# logica.net
KiCad netlist of a schematic drawn in EAGLE
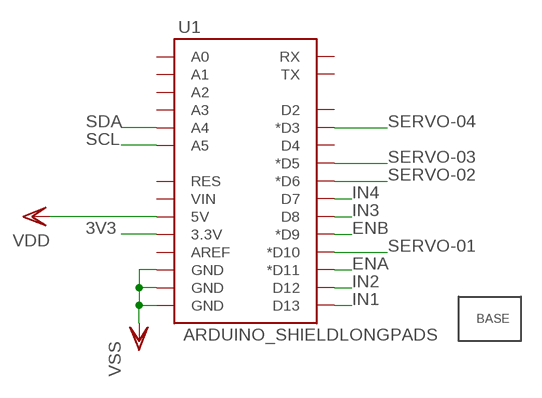
[diagram p0: schematic, sheet 1]
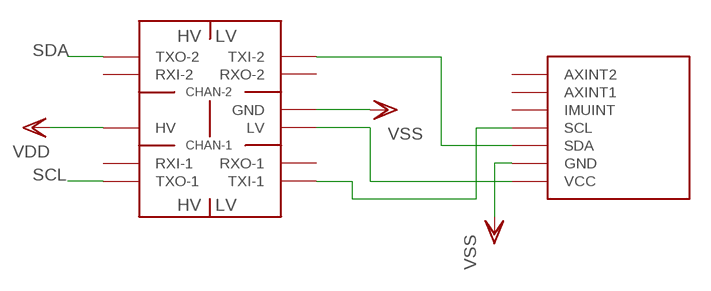
[diagram p1: schematic, sheet 2]
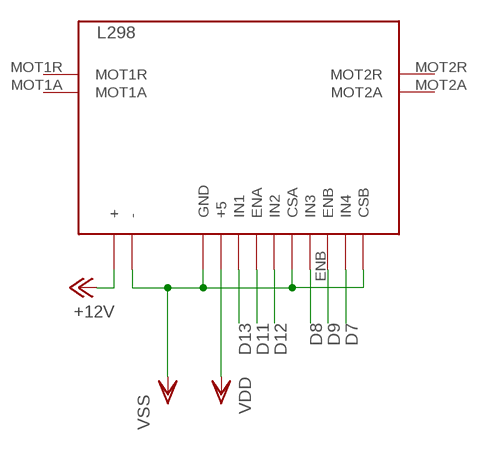
[diagram p2: schematic, sheet 3]

(export (version "E")
  (design (tool "Eeschema 10.0.6"))
  (components
    (comp (ref "L298")
      (value "UK1122")
      (footprint "eagle-import:UK1122")
      (libsource (lib "eagle-import") (part "UK1122"))
    )
    (comp (ref "U$4")
      (value "BASE")
      (footprint "eagle-import:BASE")
      (libsource (lib "eagle-import") (part "BASE"))
    )
    (comp (ref "U1")
      (value "ARDUINO_SHIELDLONGPADS")
      (footprint "eagle-import:DUEMILANOVE_SHIELD_LONGPADS")
      (libsource (lib "eagle-import") (part "ARDUINO_SHIELDLONGPADS"))
    )
    (comp (ref "U$1")
      (value "LOGIC-LEVEL-CONVERTER")
      (footprint "eagle-import:LEVEL-CONVERTER")
      (libsource (lib "eagle-import") (part "LOGIC-LEVEL-CONVERTER"))
    )
    (comp (ref "U$2")
      (value "IMU3000COMBO")
      (footprint "eagle-import:IMU3000-COMBO")
      (libsource (lib "eagle-import") (part "IMU3000COMBO"))
    )
  )
  (nets
    (net (code "1") (name "+12V") (class "Default")
      (node (ref "L298") (pin "+") (pinfunction "+_+") (pintype "power_in"))
    )
    (net (code "2") (name "3V3") (class "Default")
      (node (ref "U$1") (pin "P$3") (pinfunction "LV_P$3") (pintype "power_in"))
      (node (ref "U$2") (pin "3V3") (pinfunction "VCC_3V3") (pintype "power_in"))
      (node (ref "U1") (pin "3.3V") (pinfunction "3.3V_3.3V") (pintype "bidirectional"))
    )
    (net (code "3") (name "D7") (class "Default")
      (node (ref "L298") (pin "IN4") (pinfunction "IN4_IN4") (pintype "input"))
      (node (ref "U1") (pin "D7") (pinfunction "D7_D7") (pintype "bidirectional"))
    )
    (net (code "4") (name "D8") (class "Default")
      (node (ref "L298") (pin "IN3") (pinfunction "IN3_IN3") (pintype "input"))
      (node (ref "U1") (pin "D8") (pinfunction "D8_D8") (pintype "bidirectional"))
    )
    (net (code "5") (name "D9") (class "Default")
      (node (ref "L298") (pin "ENB") (pinfunction "ENB_ENB") (pintype "bidirectional"))
      (node (ref "U1") (pin "D9") (pinfunction "*D9_D9") (pintype "bidirectional"))
    )
    (net (code "6") (name "D11") (class "Default")
      (node (ref "L298") (pin "ENA") (pinfunction "ENA_ENA") (pintype "input"))
      (node (ref "U1") (pin "D11") (pinfunction "*D11_D11") (pintype "bidirectional"))
    )
    (net (code "7") (name "D12") (class "Default")
      (node (ref "L298") (pin "EN2") (pinfunction "IN2_EN2") (pintype "input"))
      (node (ref "U1") (pin "D12") (pinfunction "D12_D12") (pintype "bidirectional"))
    )
    (net (code "8") (name "D13") (class "Default")
      (node (ref "L298") (pin "IN1") (pinfunction "IN1_IN1") (pintype "input"))
      (node (ref "U1") (pin "D13") (pinfunction "D13_D13") (pintype "bidirectional"))
    )
    (net (code "9") (name "Net-(U$1-TXI-1)") (class "Default")
      (node (ref "U$1") (pin "P$1") (pinfunction "TXI-1_P$1") (pintype "bidirectional"))
      (node (ref "U$2") (pin "SCL") (pinfunction "SCL_SCL") (pintype "bidirectional"))
    )
    (net (code "10") (name "Net-(U$1-TXI-2)") (class "Default")
      (node (ref "U$1") (pin "P$6") (pinfunction "TXI-2_P$6") (pintype "bidirectional"))
      (node (ref "U$2") (pin "SDA") (pinfunction "SDA_SDA") (pintype "bidirectional"))
    )
    (net (code "11") (name "SCL") (class "Default")
      (node (ref "U$1") (pin "P$12") (pinfunction "TXO-1_P$12") (pintype "bidirectional"))
      (node (ref "U1") (pin "A5") (pinfunction "A5_A5") (pintype "bidirectional"))
    )
    (net (code "12") (name "SDA") (class "Default")
      (node (ref "U$1") (pin "P$7") (pinfunction "TXO-2_P$7") (pintype "bidirectional"))
      (node (ref "U1") (pin "A4") (pinfunction "A4_A4") (pintype "bidirectional"))
    )
    (net (code "13") (name "SERVO-01") (class "Default")
      (node (ref "U1") (pin "D10") (pinfunction "*D10_D10") (pintype "bidirectional"))
    )
    (net (code "14") (name "SERVO-02") (class "Default")
      (node (ref "U1") (pin "D6") (pinfunction "*D6_D6") (pintype "bidirectional"))
    )
    (net (code "15") (name "SERVO-03") (class "Default")
      (node (ref "U1") (pin "D5") (pinfunction "*D5_D5") (pintype "bidirectional"))
    )
    (net (code "16") (name "SERVO-04") (class "Default")
      (node (ref "U1") (pin "D3") (pinfunction "*D3_D3") (pintype "bidirectional"))
    )
    (net (code "17") (name "VDD") (class "Default")
      (node (ref "L298") (pin "+5") (pinfunction "+5_+5") (pintype "power_in"))
      (node (ref "U$1") (pin "P$10") (pinfunction "HV_P$10") (pintype "power_in"))
      (node (ref "U1") (pin "5V") (pinfunction "5V_5V") (pintype "bidirectional"))
    )
    (net (code "18") (name "VSS") (class "Default")
      (node (ref "L298") (pin "-") (pinfunction "-_-") (pintype "power_in"))
      (node (ref "L298") (pin "CSA") (pinfunction "CSA_CSA") (pintype "output"))
      (node (ref "L298") (pin "CSB") (pinfunction "CSB_CSB") (pintype "output"))
      (node (ref "L298") (pin "GND") (pinfunction "GND_GND") (pintype "power_in"))
      (node (ref "U$1") (pin "P$4") (pinfunction "GND_P$4") (pintype "power_in"))
      (node (ref "U$2") (pin "VSS") (pinfunction "GND_VSS") (pintype "power_in"))
      (node (ref "U1") (pin "GND@0") (pinfunction "GND_GND@0") (pintype "bidirectional"))
      (node (ref "U1") (pin "GND@1") (pinfunction "GND_GND@1") (pintype "bidirectional"))
      (node (ref "U1") (pin "GND@2") (pinfunction "GND_GND@2") (pintype "bidirectional"))
    )
    (net (code "19") (name "unconnected-(L298-PadMOT1A)") (class "Default")
      (node (ref "L298") (pin "MOT1A") (pinfunction "MOT1A_MOT1A") (pintype "bidirectional"))
    )
    (net (code "20") (name "unconnected-(L298-PadMOT1R)") (class "Default")
      (node (ref "L298") (pin "MOT1R") (pinfunction "MOT1R_MOT1R") (pintype "bidirectional"))
    )
    (net (code "21") (name "unconnected-(L298-PadMOT2A)") (class "Default")
      (node (ref "L298") (pin "MOT2A") (pinfunction "MOT2A_MOT2A") (pintype "bidirectional"))
    )
    (net (code "22") (name "unconnected-(L298-PadMOT2R)") (class "Default")
      (node (ref "L298") (pin "MOT2R") (pinfunction "MOT2R_MOT2R") (pintype "bidirectional"))
    )
    (net (code "23") (name "unconnected-(U$1-PadP$9)") (class "Default")
      (node (ref "U$1") (pin "P$9") (pintype "power_in"))
    )
    (net (code "24") (name "unconnected-(U$1-RXI-1-PadP$11)") (class "Default")
      (node (ref "U$1") (pin "P$11") (pinfunction "RXI-1_P$11") (pintype "bidirectional"))
    )
    (net (code "25") (name "unconnected-(U$1-RXI-2-PadP$8)") (class "Default")
      (node (ref "U$1") (pin "P$8") (pinfunction "RXI-2_P$8") (pintype "bidirectional"))
    )
    (net (code "26") (name "unconnected-(U$1-RXO-1-PadP$2)") (class "Default")
      (node (ref "U$1") (pin "P$2") (pinfunction "RXO-1_P$2") (pintype "bidirectional"))
    )
    (net (code "27") (name "unconnected-(U$1-RXO-2-PadP$5)") (class "Default")
      (node (ref "U$1") (pin "P$5") (pinfunction "RXO-2_P$5") (pintype "bidirectional"))
    )
    (net (code "28") (name "unconnected-(U$2-PadAXINT1)") (class "Default")
      (node (ref "U$2") (pin "AXINT1") (pinfunction "AXINT1_AXINT1") (pintype "bidirectional"))
    )
    (net (code "29") (name "unconnected-(U$2-PadAXINT2)") (class "Default")
      (node (ref "U$2") (pin "AXINT2") (pinfunction "AXINT2_AXINT2") (pintype "bidirectional"))
    )
    (net (code "30") (name "unconnected-(U$2-PadIMUINT)") (class "Default")
      (node (ref "U$2") (pin "IMUINT") (pinfunction "IMUINT_IMUINT") (pintype "bidirectional"))
    )
    (net (code "31") (name "unconnected-(U1-PadA0)") (class "Default")
      (node (ref "U1") (pin "A0") (pinfunction "A0_A0") (pintype "bidirectional"))
    )
    (net (code "32") (name "unconnected-(U1-PadA1)") (class "Default")
      (node (ref "U1") (pin "A1") (pinfunction "A1_A1") (pintype "bidirectional"))
    )
    (net (code "33") (name "unconnected-(U1-PadA2)") (class "Default")
      (node (ref "U1") (pin "A2") (pinfunction "A2_A2") (pintype "bidirectional"))
    )
    (net (code "34") (name "unconnected-(U1-PadA3)") (class "Default")
      (node (ref "U1") (pin "A3") (pinfunction "A3_A3") (pintype "bidirectional"))
    )
    (net (code "35") (name "unconnected-(U1-PadAREF)") (class "Default")
      (node (ref "U1") (pin "AREF") (pinfunction "AREF_AREF") (pintype "bidirectional"))
    )
    (net (code "36") (name "unconnected-(U1-PadD2)") (class "Default")
      (node (ref "U1") (pin "D2") (pinfunction "D2_D2") (pintype "bidirectional"))
    )
    (net (code "37") (name "unconnected-(U1-PadD4)") (class "Default")
      (node (ref "U1") (pin "D4") (pinfunction "D4_D4") (pintype "bidirectional"))
    )
    (net (code "38") (name "unconnected-(U1-PadRES)") (class "Default")
      (node (ref "U1") (pin "RES") (pinfunction "RES_RES") (pintype "bidirectional"))
    )
    (net (code "39") (name "unconnected-(U1-PadRX)") (class "Default")
      (node (ref "U1") (pin "RX") (pinfunction "RX_RX") (pintype "bidirectional"))
    )
    (net (code "40") (name "unconnected-(U1-PadTX)") (class "Default")
      (node (ref "U1") (pin "TX") (pinfunction "TX_TX") (pintype "bidirectional"))
    )
    (net (code "41") (name "unconnected-(U1-PadVIN)") (class "Default")
      (node (ref "U1") (pin "VIN") (pinfunction "VIN_VIN") (pintype "bidirectional"))
    )
  )
)
